# 1_-_main.net
KiCad netlist of a schematic drawn in Altium Designer
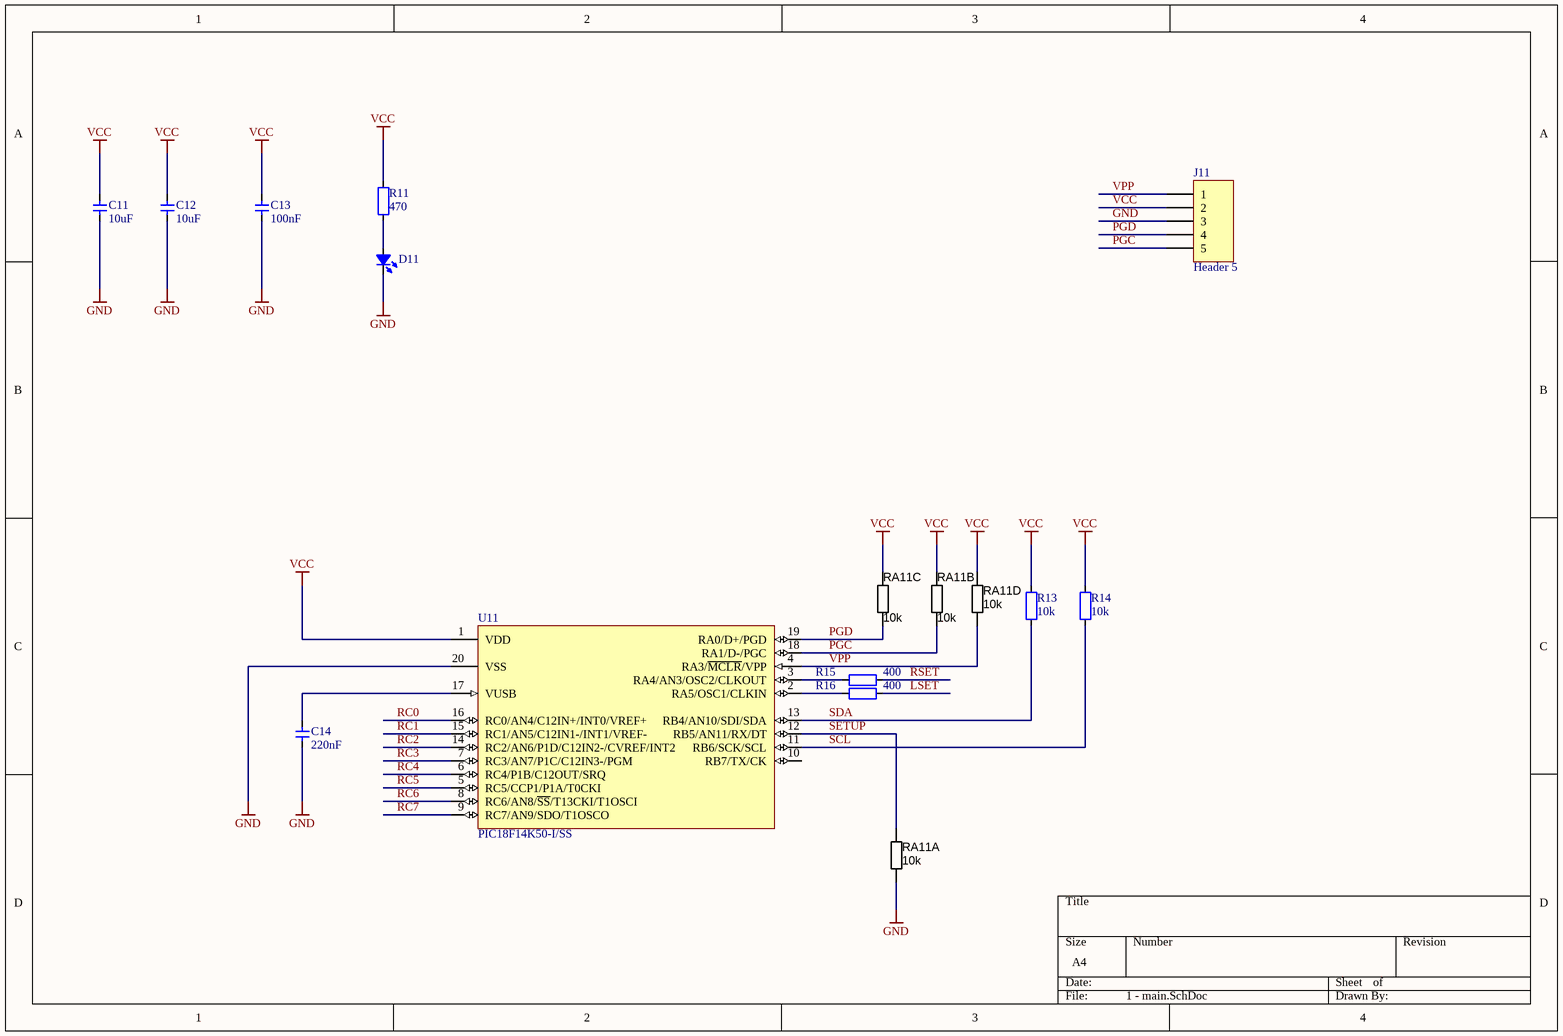
[diagram p0: 1 - main.SchDoc]

(export (version "E")
  (design (tool "Eeschema 10.0.6"))
  (components
    (comp (ref "C11")
      (value "10uF")
      (footprint "PCB_PassiveCap:CAP_0603")
      (description "Capacitor")
      (fields (field (name "Comment") "Cap_0603"))
      (libsource (lib "SCH_Passive") (part "Cap_0603"))
    )
    (comp (ref "C12")
      (value "10uF")
      (footprint "PCB_PassiveCap:CAP_0603")
      (description "Capacitor")
      (fields (field (name "Comment") "Cap_0603"))
      (libsource (lib "SCH_Passive") (part "Cap_0603"))
    )
    (comp (ref "C13")
      (value "100nF")
      (footprint "PCB_PassiveCap:CAP_0603")
      (description "Capacitor")
      (fields (field (name "Comment") "Cap_0603"))
      (libsource (lib "SCH_Passive") (part "Cap_0603"))
    )
    (comp (ref "C14")
      (value "220nF")
      (footprint "PCB_PassiveCap:CAP_0603")
      (description "Capacitor")
      (fields (field (name "Comment") "Cap_0603"))
      (libsource (lib "SCH_Passive") (part "Cap_0603"))
    )
    (comp (ref "D11")
      (value "LED_0603")
      (footprint "PCB_ActiveLED:LED_0603_RED")
      (description "LED")
      (libsource (lib "SCH_Active") (part "LED_0603"))
    )
    (comp (ref "J11")
      (value "Header 5")
      (footprint "HDR1X5")
      (description "Header, 5-Pin")
      (fields (field (name "PUBLISHER") "Altium Limited"))
      (libsource (lib "Miscellaneous Connectors") (part "Header 5"))
    )
    (comp (ref "R11")
      (value "470")
      (footprint "PCB_PassiveRes:RES_0603")
      (description "Resistor")
      (fields (field (name "Comment") "Res_0603"))
      (libsource (lib "SCH_Passive") (part "Res_0603"))
    )
    (comp (ref "R13")
      (value "10k")
      (footprint "PCB_PassiveRes:RES_0603")
      (description "Resistor")
      (fields (field (name "Comment") "Res_0603"))
      (libsource (lib "SCH_Passive") (part "Res_0603"))
    )
    (comp (ref "R14")
      (value "10k")
      (footprint "PCB_PassiveRes:RES_0603")
      (description "Resistor")
      (fields (field (name "Comment") "Res_0603"))
      (libsource (lib "SCH_Passive") (part "Res_0603"))
    )
    (comp (ref "R15")
      (value "400")
      (footprint "PCB_PassiveRes:RES_0603")
      (description "Resistor")
      (fields (field (name "Comment") "Res_0603"))
      (libsource (lib "") (part "Res_0603_1"))
    )
    (comp (ref "R16")
      (value "400")
      (footprint "PCB_PassiveRes:RES_0603")
      (description "Resistor")
      (fields (field (name "Comment") "Res_0603"))
      (libsource (lib "") (part "Res_0603_1"))
    )
    (comp (ref "RA11")
      (value "10k")
      (footprint "RESCAXS50P160X320X70-8N")
      (description "Resistor array 1K Ohm 4-pack 62.5mW 5% 4x1608 SMD")
      (fields (field (name "TOLERANCE") "±5%") (field (name "Comment") "Film Res Pack"))
      (libsource (lib "PBL - Resistors") (part "RESPACK_1K_5%_4X"))
    )
    (comp (ref "U11")
      (value "PIC18F14K50-I/SS")
      (footprint "SSOP-SS20_N")
      (description "USB Flash Microcontroller with nanoWatt XLP Technology, 20-pin SSOP, Industrial Temperature")
      (fields (field (name "PUBLISHER") "Altium Limited"))
      (libsource (lib "Microchip Microcontroller 8-Bit PIC18") (part "PIC18F14K50-I/SS"))
    )
  )
  (nets
    (net (code "1") (name "/LSET") (class "Default")
      (node (ref "R16") (pin "1") (pinfunction "1_1") (pintype "passive"))
    )
    (net (code "2") (name "/PGC") (class "Default")
      (node (ref "J11") (pin "5") (pinfunction "5_5") (pintype "passive"))
      (node (ref "RA11") (pin "2") (pinfunction "2_2") (pintype "passive"))
      (node (ref "U11") (pin "18") (pinfunction "RA1/D-/PGC_18") (pintype "bidirectional"))
    )
    (net (code "3") (name "/PGD") (class "Default")
      (node (ref "J11") (pin "4") (pinfunction "4_4") (pintype "passive"))
      (node (ref "RA11") (pin "3") (pinfunction "3_3") (pintype "passive"))
      (node (ref "U11") (pin "19") (pinfunction "RA0/D+/PGD_19") (pintype "bidirectional"))
    )
    (net (code "4") (name "/RC0") (class "Default")
      (node (ref "U11") (pin "16") (pinfunction "RC0/AN4/C12IN+/INT0/VREF+_16") (pintype "bidirectional"))
    )
    (net (code "5") (name "/RC1") (class "Default")
      (node (ref "U11") (pin "15") (pinfunction "RC1/AN5/C12IN1-/INT1/VREF-_15") (pintype "bidirectional"))
    )
    (net (code "6") (name "/RC2") (class "Default")
      (node (ref "U11") (pin "14") (pinfunction "RC2/AN6/P1D/C12IN2-/CVREF/INT2_14") (pintype "bidirectional"))
    )
    (net (code "7") (name "/RC3") (class "Default")
      (node (ref "U11") (pin "7") (pinfunction "RC3/AN7/P1C/C12IN3-/PGM_7") (pintype "bidirectional"))
    )
    (net (code "8") (name "/RC4") (class "Default")
      (node (ref "U11") (pin "6") (pinfunction "RC4/P1B/C12OUT/SRQ_6") (pintype "bidirectional"))
    )
    (net (code "9") (name "/RC5") (class "Default")
      (node (ref "U11") (pin "5") (pinfunction "RC5/CCP1/P1A/T0CKI_5") (pintype "bidirectional"))
    )
    (net (code "10") (name "/RC6") (class "Default")
      (node (ref "U11") (pin "8") (pinfunction "RC6/AN8/~{SS}/T13CKI/T1OSCI_8") (pintype "bidirectional"))
    )
    (net (code "11") (name "/RC7") (class "Default")
      (node (ref "U11") (pin "9") (pinfunction "RC7/AN9/SDO/T1OSCO_9") (pintype "bidirectional"))
    )
    (net (code "12") (name "/RSET") (class "Default")
      (node (ref "R15") (pin "1") (pinfunction "1_1") (pintype "passive"))
    )
    (net (code "13") (name "/SCL") (class "Default")
      (node (ref "R14") (pin "1") (pinfunction "1_1") (pintype "passive"))
      (node (ref "U11") (pin "11") (pinfunction "RB6/SCK/SCL_11") (pintype "bidirectional"))
    )
    (net (code "14") (name "/SDA") (class "Default")
      (node (ref "R13") (pin "1") (pinfunction "1_1") (pintype "passive"))
      (node (ref "U11") (pin "13") (pinfunction "RB4/AN10/SDI/SDA_13") (pintype "bidirectional"))
    )
    (net (code "15") (name "/SETUP") (class "Default")
      (node (ref "RA11") (pin "1") (pinfunction "1_1") (pintype "passive"))
      (node (ref "U11") (pin "12") (pinfunction "RB5/AN11/RX/DT_12") (pintype "bidirectional"))
    )
    (net (code "16") (name "/VPP") (class "Default")
      (node (ref "J11") (pin "1") (pinfunction "1_1") (pintype "passive"))
      (node (ref "RA11") (pin "4") (pinfunction "4_4") (pintype "passive"))
      (node (ref "U11") (pin "4") (pinfunction "RA3/~{MCLR}/VPP_4") (pintype "input"))
    )
    (net (code "17") (name "GND") (class "Default")
      (node (ref "C11") (pin "1") (pinfunction "1_1") (pintype "passive"))
      (node (ref "C12") (pin "1") (pinfunction "1_1") (pintype "passive"))
      (node (ref "C13") (pin "1") (pinfunction "1_1") (pintype "passive"))
      (node (ref "C14") (pin "1") (pinfunction "1_1") (pintype "passive"))
      (node (ref "D11") (pin "2") (pinfunction "K_2") (pintype "passive"))
      (node (ref "J11") (pin "3") (pinfunction "3_3") (pintype "passive"))
      (node (ref "RA11") (pin "8") (pinfunction "8_8") (pintype "passive"))
      (node (ref "U11") (pin "20") (pinfunction "VSS_20") (pintype "power_in"))
    )
    (net (code "18") (name "Net-(D11-A)") (class "Default")
      (node (ref "D11") (pin "1") (pinfunction "A_1") (pintype "passive"))
      (node (ref "R11") (pin "1") (pinfunction "1_1") (pintype "passive"))
    )
    (net (code "19") (name "Net-(U11-RA4{slash}AN3{slash}OSC2{slash}CLKOUT)") (class "Default")
      (node (ref "R15") (pin "2") (pinfunction "2_2") (pintype "passive"))
      (node (ref "U11") (pin "3") (pinfunction "RA4/AN3/OSC2/CLKOUT_3") (pintype "bidirectional"))
    )
    (net (code "20") (name "Net-(U11-RA5{slash}OSC1{slash}CLKIN)") (class "Default")
      (node (ref "R16") (pin "2") (pinfunction "2_2") (pintype "passive"))
      (node (ref "U11") (pin "2") (pinfunction "RA5/OSC1/CLKIN_2") (pintype "bidirectional"))
    )
    (net (code "21") (name "Net-(U11-VUSB)") (class "Default")
      (node (ref "C14") (pin "2") (pinfunction "2_2") (pintype "passive"))
      (node (ref "U11") (pin "17") (pinfunction "VUSB_17") (pintype "input"))
    )
    (net (code "22") (name "VCC") (class "Default")
      (node (ref "C11") (pin "2") (pinfunction "2_2") (pintype "passive"))
      (node (ref "C12") (pin "2") (pinfunction "2_2") (pintype "passive"))
      (node (ref "C13") (pin "2") (pinfunction "2_2") (pintype "passive"))
      (node (ref "J11") (pin "2") (pinfunction "2_2") (pintype "passive"))
      (node (ref "R11") (pin "2") (pinfunction "2_2") (pintype "passive"))
      (node (ref "R13") (pin "2") (pinfunction "2_2") (pintype "passive"))
      (node (ref "R14") (pin "2") (pinfunction "2_2") (pintype "passive"))
      (node (ref "RA11") (pin "5") (pinfunction "5_5") (pintype "passive"))
      (node (ref "RA11") (pin "6") (pinfunction "6_6") (pintype "passive"))
      (node (ref "RA11") (pin "7") (pinfunction "7_7") (pintype "passive"))
      (node (ref "U11") (pin "1") (pinfunction "VDD_1") (pintype "power_in"))
    )
    (net (code "23") (name "unconnected-(U11-RB7{slash}TX{slash}CK-Pad10)") (class "Default")
      (node (ref "U11") (pin "10") (pinfunction "RB7/TX/CK_10") (pintype "bidirectional"))
    )
  )
)
